# Schaltplan.net
KiCad netlist of a schematic drawn in EAGLE
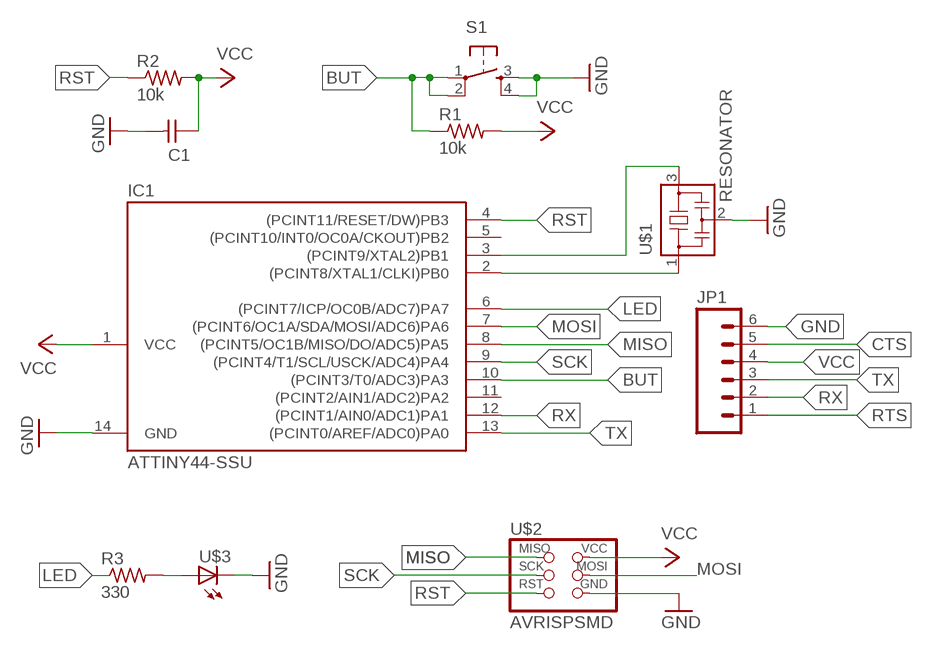
[diagram p0: schematic, sheet 1]

(export (version "E")
  (design (tool "Eeschema 10.0.6"))
  (components
    (comp (ref "C1")
      (value "UNPOLARIZED_CAPACITOR1206")
      (footprint "eagle-import:1206")
      (libsource (lib "eagle-import") (part "UNPOLARIZED_CAPACITOR1206"))
    )
    (comp (ref "IC1")
      (value "ATTINY44-SSU")
      (footprint "eagle-import:SOIC14")
      (libsource (lib "eagle-import") (part "ATTINY44-SSU"))
    )
    (comp (ref "JP1")
      (value "M06SMD")
      (footprint "eagle-import:1X06-SMD")
      (libsource (lib "eagle-import") (part "M06SMD"))
    )
    (comp (ref "R1")
      (value "10k")
      (footprint "eagle-import:1206")
      (libsource (lib "eagle-import") (part "RESISTOR1206"))
    )
    (comp (ref "R2")
      (value "10k")
      (footprint "eagle-import:1206")
      (libsource (lib "eagle-import") (part "RESISTOR1206"))
    )
    (comp (ref "R3")
      (value "330")
      (footprint "eagle-import:1206")
      (libsource (lib "eagle-import") (part "RESISTOR1206"))
    )
    (comp (ref "S1")
      (value "6MM_SWITCH6MM_SWITCH")
      (footprint "eagle-import:6MM_SWITCH")
      (libsource (lib "eagle-import") (part "6MM_SWITCH6MM_SWITCH"))
    )
    (comp (ref "U$1")
      (value "RESONATOR")
      (footprint "eagle-import:EFOBM")
      (libsource (lib "eagle-import") (part "RESONATOR"))
    )
    (comp (ref "U$2")
      (value "AVRISPSMD")
      (footprint "eagle-import:2X03SMD")
      (libsource (lib "eagle-import") (part "AVRISPSMD"))
    )
    (comp (ref "U$3")
      (value "LED1206")
      (footprint "eagle-import:1206")
      (libsource (lib "eagle-import") (part "LED1206"))
    )
  )
  (nets
    (net (code "1") (name "BUT") (class "Default")
      (node (ref "IC1") (pin "10") (pinfunction "(PCINT3/T0/ADC3)PA3_10") (pintype "bidirectional"))
      (node (ref "R1") (pin "1") (pinfunction "1_1") (pintype "passive"))
      (node (ref "S1") (pin "1") (pinfunction "P_1") (pintype "passive"))
      (node (ref "S1") (pin "2") (pinfunction "P1_2") (pintype "passive"))
    )
    (net (code "2") (name "CTS") (class "Default")
      (node (ref "JP1") (pin "5") (pinfunction "5_5") (pintype "passive"))
    )
    (net (code "3") (name "GND") (class "Default")
      (node (ref "C1") (pin "2") (pinfunction "2_2") (pintype "passive"))
      (node (ref "IC1") (pin "14") (pinfunction "GND_14") (pintype "power_in"))
      (node (ref "JP1") (pin "6") (pinfunction "6_6") (pintype "passive"))
      (node (ref "S1") (pin "3") (pinfunction "S_3") (pintype "passive"))
      (node (ref "S1") (pin "4") (pinfunction "S1_4") (pintype "passive"))
      (node (ref "U$1") (pin "2") (pinfunction "2_2") (pintype "passive"))
      (node (ref "U$2") (pin "6") (pinfunction "GND_6") (pintype "passive"))
      (node (ref "U$3") (pin "2") (pinfunction "C_2") (pintype "passive"))
    )
    (net (code "4") (name "LED") (class "Default")
      (node (ref "IC1") (pin "6") (pinfunction "(PCINT7/ICP/OC0B/ADC7)PA7_6") (pintype "bidirectional"))
      (node (ref "R3") (pin "1") (pinfunction "1_1") (pintype "passive"))
    )
    (net (code "5") (name "MISO") (class "Default")
      (node (ref "IC1") (pin "8") (pinfunction "(PCINT5/OC1B/MISO/DO/ADC5)PA5_8") (pintype "bidirectional"))
      (node (ref "U$2") (pin "1") (pinfunction "MISO_1") (pintype "passive"))
    )
    (net (code "6") (name "MOSI") (class "Default")
      (node (ref "IC1") (pin "7") (pinfunction "(PCINT6/OC1A/SDA/MOSI/ADC6)PA6_7") (pintype "bidirectional"))
      (node (ref "U$2") (pin "4") (pinfunction "MOSI_4") (pintype "passive"))
    )
    (net (code "7") (name "Net-(IC1-(PCINT8{slash}XTAL1{slash}CLKI)PB0)") (class "Default")
      (node (ref "IC1") (pin "2") (pinfunction "(PCINT8/XTAL1/CLKI)PB0_2") (pintype "bidirectional"))
      (node (ref "U$1") (pin "1") (pinfunction "1_1") (pintype "passive"))
    )
    (net (code "8") (name "Net-(IC1-(PCINT9{slash}XTAL2)PB1)") (class "Default")
      (node (ref "IC1") (pin "3") (pinfunction "(PCINT9/XTAL2)PB1_3") (pintype "bidirectional"))
      (node (ref "U$1") (pin "3") (pinfunction "3_3") (pintype "passive"))
    )
    (net (code "9") (name "Net-(U$3-A)") (class "Default")
      (node (ref "R3") (pin "2") (pinfunction "2_2") (pintype "passive"))
      (node (ref "U$3") (pin "1") (pinfunction "A_1") (pintype "passive"))
    )
    (net (code "10") (name "RST") (class "Default")
      (node (ref "IC1") (pin "4") (pinfunction "(PCINT11/RESET/DW)PB3_4") (pintype "bidirectional"))
      (node (ref "R2") (pin "1") (pinfunction "1_1") (pintype "passive"))
      (node (ref "U$2") (pin "5") (pinfunction "RST_5") (pintype "passive"))
    )
    (net (code "11") (name "RTS") (class "Default")
      (node (ref "JP1") (pin "1") (pinfunction "1_1") (pintype "passive"))
    )
    (net (code "12") (name "RX") (class "Default")
      (node (ref "IC1") (pin "12") (pinfunction "(PCINT1/AIN0/ADC1)PA1_12") (pintype "bidirectional"))
      (node (ref "JP1") (pin "2") (pinfunction "2_2") (pintype "passive"))
    )
    (net (code "13") (name "SCK") (class "Default")
      (node (ref "IC1") (pin "9") (pinfunction "(PCINT4/T1/SCL/USCK/ADC4)PA4_9") (pintype "bidirectional"))
      (node (ref "U$2") (pin "3") (pinfunction "SCK_3") (pintype "passive"))
    )
    (net (code "14") (name "TX") (class "Default")
      (node (ref "IC1") (pin "13") (pinfunction "(PCINT0/AREF/ADC0)PA0_13") (pintype "bidirectional"))
      (node (ref "JP1") (pin "3") (pinfunction "3_3") (pintype "passive"))
    )
    (net (code "15") (name "VCC") (class "Default")
      (node (ref "C1") (pin "1") (pinfunction "1_1") (pintype "passive"))
      (node (ref "IC1") (pin "1") (pinfunction "VCC_1") (pintype "power_in"))
      (node (ref "JP1") (pin "4") (pinfunction "4_4") (pintype "passive"))
      (node (ref "R1") (pin "2") (pinfunction "2_2") (pintype "passive"))
      (node (ref "R2") (pin "2") (pinfunction "2_2") (pintype "passive"))
      (node (ref "U$2") (pin "2") (pinfunction "VCC_2") (pintype "passive"))
    )
    (net (code "16") (name "unconnected-(IC1-(PCINT2{slash}AIN1{slash}ADC2)PA2-Pad11)") (class "Default")
      (node (ref "IC1") (pin "11") (pinfunction "(PCINT2/AIN1/ADC2)PA2_11") (pintype "bidirectional"))
    )
    (net (code "17") (name "unconnected-(IC1-(PCINT10{slash}INT0{slash}OC0A{slash}CKOUT)PB2-Pad5)") (class "Default")
      (node (ref "IC1") (pin "5") (pinfunction "(PCINT10/INT0/OC0A/CKOUT)PB2_5") (pintype "bidirectional"))
    )
  )
)
